# Gyro_Accel_Temp_MPU6050.net
KiCad netlist of a schematic drawn in Altium Designer
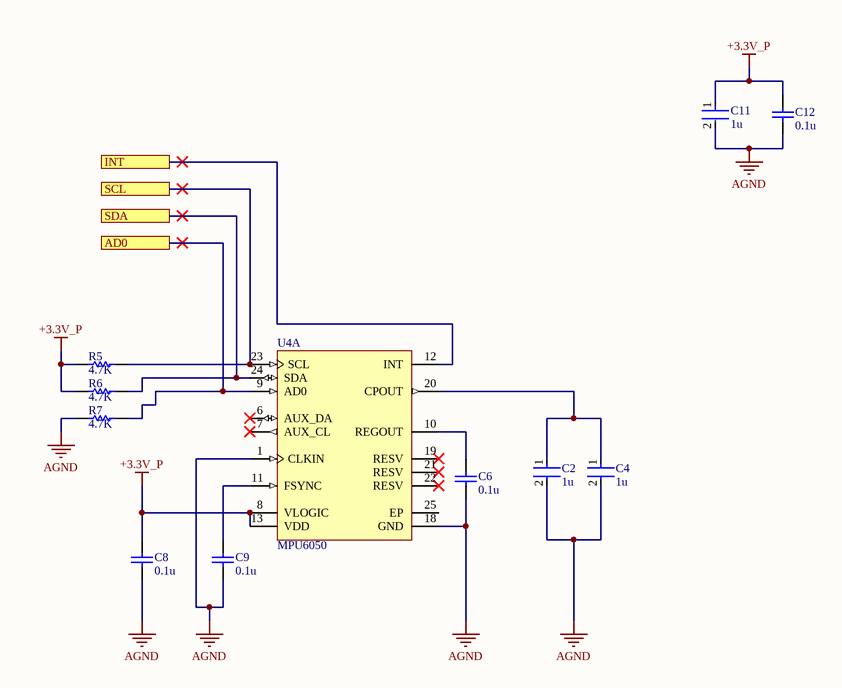
[diagram p0: Gyro Accel Temp MPU6050.SchDoc]

(export (version "E")
  (design (tool "Eeschema 10.0.6"))
  (components
    (comp (ref "C2")
      (value "1u")
      (footprint "FP-CL31-IPC_B")
      (description "Cap Ceramic 1uF 50V X7R ±10% SMD 1206 +125°C Embossed T/R")
      (fields (field (name "VOLTAGE") "50V") (field (name "TOLERANCE") "10%"))
      (libsource (lib "Altium Content Vault") (part "b4654b650e69147ec39a6b967a45e02"))
    )
    (comp (ref "C4")
      (value "1u")
      (footprint "FP-CL31-IPC_B")
      (description "Cap Ceramic 1uF 50V X7R ±10% SMD 1206 +125°C Embossed T/R")
      (fields (field (name "VOLTAGE") "50V") (field (name "TOLERANCE") "10%"))
      (libsource (lib "Altium Content Vault") (part "b4654b650e69147ec39a6b967a45e02"))
    )
    (comp (ref "C6")
      (value "0.1u")
      (footprint "CAPC1206(3216)130_M")
      (description "CAP 100nF 100V ±20% 1206 (3216 Metric) Thickness 1.3mm SMD")
      (fields (field (name "TOLERANCE") "Â±20%"))
      (libsource (lib "Altium Content Vault") (part "CAP"))
    )
    (comp (ref "C8")
      (value "0.1u")
      (footprint "CAPC1206(3216)130_M")
      (description "CAP 100nF 100V ±20% 1206 (3216 Metric) Thickness 1.3mm SMD")
      (fields (field (name "TOLERANCE") "Â±20%"))
      (libsource (lib "Altium Content Vault") (part "CAP"))
    )
    (comp (ref "C9")
      (value "0.1u")
      (footprint "CAPC1206(3216)130_M")
      (description "CAP 100nF 100V ±20% 1206 (3216 Metric) Thickness 1.3mm SMD")
      (fields (field (name "TOLERANCE") "Â±20%"))
      (libsource (lib "Altium Content Vault") (part "CAP"))
    )
    (comp (ref "C11")
      (value "1u")
      (footprint "FP-CL31-IPC_B")
      (description "Cap Ceramic 1uF 50V X7R ±10% SMD 1206 +125°C Embossed T/R")
      (fields (field (name "VOLTAGE") "50V") (field (name "TOLERANCE") "10%"))
      (libsource (lib "Altium Content Vault") (part "b4654b650e69147ec39a6b967a45e02"))
    )
    (comp (ref "C12")
      (value "0.1u")
      (footprint "CAPC1206(3216)130_M")
      (description "CAP 100nF 100V ±20% 1206 (3216 Metric) Thickness 1.3mm SMD")
      (fields (field (name "TOLERANCE") "Â±20%"))
      (libsource (lib "Altium Content Vault") (part "CAP"))
    )
    (comp (ref "R5")
      (value "4.7K")
      (footprint "RESC3216X70X50LL05T20")
      (fields (field (name "PART NUMBER") "ERJ8ENF4701V") (field (name "MANUFACTURER") "Panasonic"))
      (libsource (lib "Altium Content Vault") (part "RES"))
    )
    (comp (ref "R6")
      (value "4.7K")
      (footprint "RESC3216X70X50LL05T20")
      (fields (field (name "PART NUMBER") "ERJ8ENF4701V") (field (name "MANUFACTURER") "Panasonic"))
      (libsource (lib "Altium Content Vault") (part "RES"))
    )
    (comp (ref "R7")
      (value "4.7K")
      (footprint "RESC3216X70X50LL05T20")
      (fields (field (name "PART NUMBER") "ERJ8ENF4701V") (field (name "MANUFACTURER") "Panasonic"))
      (libsource (lib "Altium Content Vault") (part "RES"))
    )
    (comp (ref "U4")
      (value "MPU6050")
      (footprint "INSE-QFN-24_V")
      (fields (field (name "TOLERANCE") "1%"))
      (libsource (lib "Altium Content Vault") (part "INSE-MPU6050-QFN-24"))
    )
  )
  (nets
    (net (code "1") (name "+3.3V_P") (class "Default")
      (node (ref "C11") (pin "1") (pinfunction "1_1") (pintype "passive"))
      (node (ref "C12") (pin "2") (pinfunction "2_2") (pintype "passive"))
      (node (ref "C8") (pin "2") (pinfunction "2_2") (pintype "passive"))
      (node (ref "R5") (pin "1") (pinfunction "1_1") (pintype "passive"))
      (node (ref "R6") (pin "1") (pinfunction "1_1") (pintype "passive"))
      (node (ref "U4") (pin "13") (pinfunction "VDD_13") (pintype "power_in"))
      (node (ref "U4") (pin "8") (pinfunction "VLOGIC_8") (pintype "power_in"))
    )
    (net (code "2") (name "/AD0") (class "Default")
      (node (ref "R7") (pin "2") (pinfunction "2_2") (pintype "passive"))
      (node (ref "U4") (pin "9") (pinfunction "AD0_9") (pintype "input"))
    )
    (net (code "3") (name "/INT") (class "Default")
      (node (ref "U4") (pin "12") (pinfunction "INT_12") (pintype "open_collector"))
    )
    (net (code "4") (name "/SCL") (class "Default")
      (node (ref "R5") (pin "2") (pinfunction "2_2") (pintype "passive"))
      (node (ref "U4") (pin "23") (pinfunction "SCL_23") (pintype "input"))
    )
    (net (code "5") (name "/SDA") (class "Default")
      (node (ref "R6") (pin "2") (pinfunction "2_2") (pintype "passive"))
      (node (ref "U4") (pin "24") (pinfunction "SDA_24") (pintype "bidirectional"))
    )
    (net (code "6") (name "AGND") (class "Default")
      (node (ref "C11") (pin "2") (pinfunction "2_2") (pintype "passive"))
      (node (ref "C12") (pin "1") (pinfunction "1_1") (pintype "passive"))
      (node (ref "C2") (pin "2") (pinfunction "2_2") (pintype "passive"))
      (node (ref "C4") (pin "2") (pinfunction "2_2") (pintype "passive"))
      (node (ref "C6") (pin "1") (pinfunction "1_1") (pintype "passive"))
      (node (ref "C8") (pin "1") (pinfunction "1_1") (pintype "passive"))
      (node (ref "C9") (pin "1") (pinfunction "1_1") (pintype "passive"))
      (node (ref "R7") (pin "1") (pinfunction "1_1") (pintype "passive"))
      (node (ref "U4") (pin "1") (pinfunction "CLKIN_1") (pintype "input"))
      (node (ref "U4") (pin "18") (pinfunction "GND_18") (pintype "power_in"))
    )
    (net (code "7") (name "Net-(U4A-CPOUT)") (class "Default")
      (node (ref "C2") (pin "1") (pinfunction "1_1") (pintype "passive"))
      (node (ref "C4") (pin "1") (pinfunction "1_1") (pintype "passive"))
      (node (ref "U4") (pin "20") (pinfunction "CPOUT_20") (pintype "output"))
    )
    (net (code "8") (name "Net-(U4A-FSYNC)") (class "Default")
      (node (ref "C9") (pin "2") (pinfunction "2_2") (pintype "passive"))
      (node (ref "U4") (pin "11") (pinfunction "FSYNC_11") (pintype "input"))
    )
    (net (code "9") (name "Net-(U4A-REGOUT)") (class "Default")
      (node (ref "C6") (pin "2") (pinfunction "2_2") (pintype "passive"))
      (node (ref "U4") (pin "10") (pinfunction "REGOUT_10") (pintype "passive"))
    )
    (net (code "10") (name "unconnected-(U4A-AUX_CL-Pad7)") (class "Default")
      (node (ref "U4") (pin "7") (pinfunction "AUX_CL_7") (pintype "output+no_connect"))
    )
    (net (code "11") (name "unconnected-(U4A-AUX_DA-Pad6)") (class "Default")
      (node (ref "U4") (pin "6") (pinfunction "AUX_DA_6") (pintype "bidirectional+no_connect"))
    )
    (net (code "12") (name "unconnected-(U4A-EP-Pad25)") (class "Default")
      (node (ref "U4") (pin "25") (pinfunction "EP_25") (pintype "passive"))
    )
    (net (code "13") (name "unconnected-(U4A-RESV-Pad19)") (class "Default")
      (node (ref "U4") (pin "19") (pinfunction "RESV_19") (pintype "passive+no_connect"))
    )
    (net (code "14") (name "unconnected-(U4A-RESV-Pad21)") (class "Default")
      (node (ref "U4") (pin "21") (pinfunction "RESV_21") (pintype "passive+no_connect"))
    )
    (net (code "15") (name "unconnected-(U4A-RESV-Pad22)") (class "Default")
      (node (ref "U4") (pin "22") (pinfunction "RESV_22") (pintype "passive+no_connect"))
    )
  )
)
